# design.net
KiCad netlist of a schematic drawn in Altium Designer
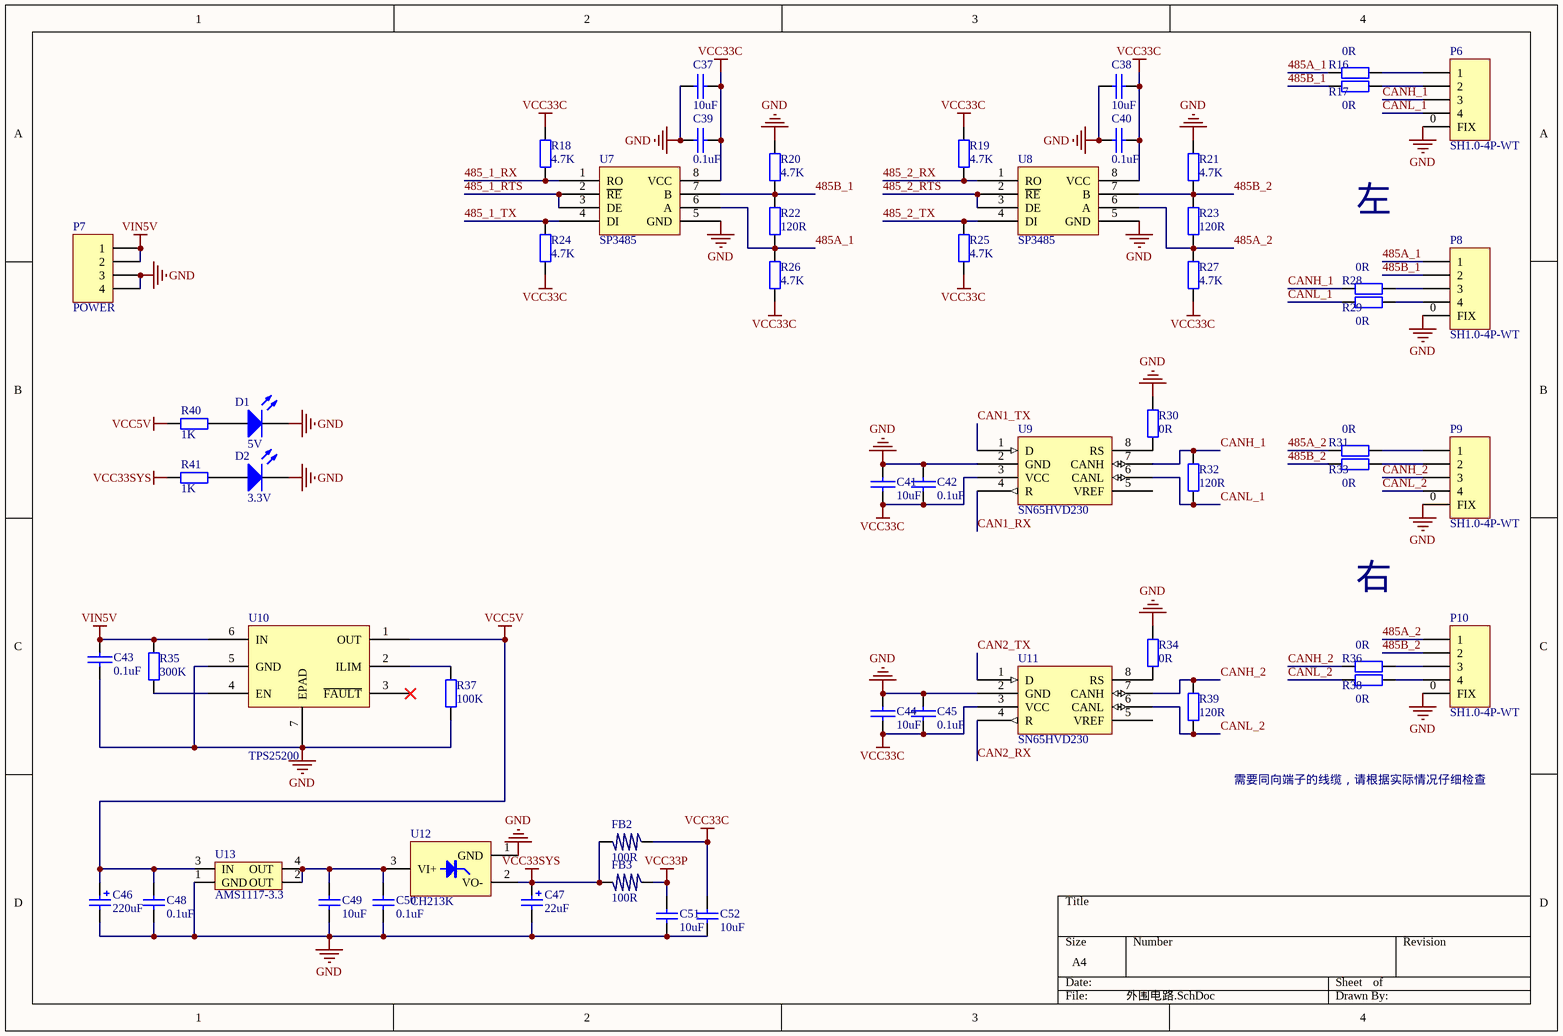
[diagram p0: 外围电路.SchDoc]

(export (version "E")
  (design (tool "Eeschema 10.0.6"))
  (components
    (comp (ref "C37")
      (value "10uF")
      (footprint "C0805_M")
      (description "Capacitor")
      (libsource (lib "*") (part "CAP"))
    )
    (comp (ref "C38")
      (value "10uF")
      (footprint "C0805_M")
      (description "Capacitor")
      (libsource (lib "*") (part "CAP"))
    )
    (comp (ref "C39")
      (value "0.1uF")
      (footprint "C0805_M")
      (description "Capacitor")
      (libsource (lib "*") (part "CAP"))
    )
    (comp (ref "C40")
      (value "0.1uF")
      (footprint "C0805_M")
      (description "Capacitor")
      (libsource (lib "*") (part "CAP"))
    )
    (comp (ref "C41")
      (value "10uF")
      (footprint "C0805_M")
      (description "Capacitor")
      (libsource (lib "*") (part "CAP"))
    )
    (comp (ref "C42")
      (value "0.1uF")
      (footprint "C0805_M")
      (description "Capacitor")
      (libsource (lib "*") (part "CAP"))
    )
    (comp (ref "C43")
      (value "0.1uF")
      (footprint "C0805_M")
      (description "Capacitor")
      (libsource (lib "*") (part "CAP"))
    )
    (comp (ref "C44")
      (value "10uF")
      (footprint "C0805_M")
      (description "Capacitor")
      (libsource (lib "*") (part "CAP"))
    )
    (comp (ref "C45")
      (value "0.1uF")
      (footprint "C0805_M")
      (description "Capacitor")
      (libsource (lib "*") (part "CAP"))
    )
    (comp (ref "C46")
      (value "220uF")
      (footprint "CS 6*6 - R")
      (description "Polarized Capacitor (Axial)")
      (fields (field (name "PUBLISHER") "Altium Limited"))
      (libsource (lib "Miscellaneous Devices") (part "Cap Pol2"))
    )
    (comp (ref "C47")
      (value "22uF")
      (footprint "CS 6*6 - R")
      (description "Polarized Capacitor (Axial)")
      (fields (field (name "PUBLISHER") "Altium Limited"))
      (libsource (lib "Miscellaneous Devices") (part "Cap Pol2"))
    )
    (comp (ref "C48")
      (value "0.1uF")
      (footprint "C0805_M")
      (description "Capacitor")
      (fields (field (name "PUBLISHER") "Altium Limited"))
      (libsource (lib "Miscellaneous Devices") (part "Cap"))
    )
    (comp (ref "C49")
      (value "10uF")
      (footprint "C0805_M")
      (description "Capacitor")
      (fields (field (name "PUBLISHER") "Altium Limited"))
      (libsource (lib "Miscellaneous Devices") (part "Cap"))
    )
    (comp (ref "C50")
      (value "0.1uF")
      (footprint "C0805_M")
      (description "Capacitor")
      (fields (field (name "PUBLISHER") "Altium Limited"))
      (libsource (lib "Miscellaneous Devices") (part "Cap"))
    )
    (comp (ref "C51")
      (value "10uF")
      (footprint "C0805_M")
      (description "Capacitor")
      (fields (field (name "PUBLISHER") "Altium Limited"))
      (libsource (lib "Miscellaneous Devices") (part "Cap"))
    )
    (comp (ref "C52")
      (value "10uF")
      (footprint "C0805_M")
      (description "Capacitor")
      (fields (field (name "PUBLISHER") "Altium Limited"))
      (libsource (lib "Miscellaneous Devices") (part "Cap"))
    )
    (comp (ref "D1")
      (value "5V")
      (footprint "LED0805_G")
      (description "Typical RED GaAs LED")
      (fields (field (name "PUBLISHER") "Altium Limited"))
      (libsource (lib "Miscellaneous Devices") (part "LED1"))
    )
    (comp (ref "D2")
      (value "3.3V")
      (footprint "LED0805_G")
      (description "Typical RED GaAs LED")
      (fields (field (name "PUBLISHER") "Altium Limited"))
      (libsource (lib "Miscellaneous Devices") (part "LED1"))
    )
    (comp (ref "FB2") (value "100R") (footprint "R0805_M") (libsource (lib "EXPLORER") (part "L")))
    (comp (ref "FB3") (value "100R") (footprint "R0805_M") (libsource (lib "EXPLORER") (part "L")))
    (comp (ref "P6")
      (value "SH1.0-4P-WT")
      (footprint "SH1.0-LT-4P")
      (description "Header, 5-Pin")
      (fields (field (name "PUBLISHER") "Altium Limited"))
      (libsource (lib "Miscellaneous Connectors") (part "Header 5"))
    )
    (comp (ref "P7")
      (value "POWER")
      (footprint "XH2.54-LI-4P")
      (description "Header, 4-Pin")
      (fields (field (name "PUBLISHER") "Altium Limited"))
      (libsource (lib "Miscellaneous Connectors") (part "Header 4"))
    )
    (comp (ref "P8")
      (value "SH1.0-4P-WT")
      (footprint "SH1.0-LT-4P")
      (description "Header, 5-Pin")
      (fields (field (name "PUBLISHER") "Altium Limited"))
      (libsource (lib "Miscellaneous Connectors") (part "Header 5"))
    )
    (comp (ref "P9")
      (value "SH1.0-4P-WT")
      (footprint "SH1.0-LT-4P")
      (description "Header, 5-Pin")
      (fields (field (name "PUBLISHER") "Altium Limited"))
      (libsource (lib "Miscellaneous Connectors") (part "Header 5"))
    )
    (comp (ref "P10")
      (value "SH1.0-4P-WT")
      (footprint "SH1.0-LT-4P")
      (description "Header, 5-Pin")
      (fields (field (name "PUBLISHER") "Altium Limited"))
      (libsource (lib "Miscellaneous Connectors") (part "Header 5"))
    )
    (comp (ref "R16")
      (value "0R")
      (footprint "R0805_M")
      (description "Resistor")
      (fields (field (name "PUBLISHER") "Altium Limited"))
      (libsource (lib "") (part "Res2_1"))
    )
    (comp (ref "R17")
      (value "0R")
      (footprint "R0805_M")
      (description "Resistor")
      (fields (field (name "PUBLISHER") "Altium Limited"))
      (libsource (lib "") (part "Res2_1"))
    )
    (comp (ref "R18")
      (value "4.7K")
      (footprint "R0805_M")
      (description "Resistor")
      (fields (field (name "PUBLISHER") "Altium Limited"))
      (libsource (lib "Miscellaneous Devices") (part "Res2"))
    )
    (comp (ref "R19")
      (value "4.7K")
      (footprint "R0805_M")
      (description "Resistor")
      (fields (field (name "PUBLISHER") "Altium Limited"))
      (libsource (lib "Miscellaneous Devices") (part "Res2"))
    )
    (comp (ref "R20")
      (value "4.7K")
      (footprint "R0805_M")
      (description "Resistor")
      (fields (field (name "PUBLISHER") "Altium Limited"))
      (libsource (lib "Miscellaneous Devices") (part "Res2"))
    )
    (comp (ref "R21")
      (value "4.7K")
      (footprint "R0805_M")
      (description "Resistor")
      (fields (field (name "PUBLISHER") "Altium Limited"))
      (libsource (lib "Miscellaneous Devices") (part "Res2"))
    )
    (comp (ref "R22")
      (value "120R")
      (footprint "R0805_M")
      (description "Resistor")
      (fields (field (name "PUBLISHER") "Altium Limited"))
      (libsource (lib "Miscellaneous Devices") (part "Res2"))
    )
    (comp (ref "R23")
      (value "120R")
      (footprint "R0805_M")
      (description "Resistor")
      (fields (field (name "PUBLISHER") "Altium Limited"))
      (libsource (lib "Miscellaneous Devices") (part "Res2"))
    )
    (comp (ref "R24")
      (value "4.7K")
      (footprint "R0805_M")
      (description "Resistor")
      (fields (field (name "PUBLISHER") "Altium Limited"))
      (libsource (lib "Miscellaneous Devices") (part "Res2"))
    )
    (comp (ref "R25")
      (value "4.7K")
      (footprint "R0805_M")
      (description "Resistor")
      (fields (field (name "PUBLISHER") "Altium Limited"))
      (libsource (lib "Miscellaneous Devices") (part "Res2"))
    )
    (comp (ref "R26")
      (value "4.7K")
      (footprint "R0805_M")
      (description "Resistor")
      (fields (field (name "PUBLISHER") "Altium Limited"))
      (libsource (lib "Miscellaneous Devices") (part "Res2"))
    )
    (comp (ref "R27")
      (value "4.7K")
      (footprint "R0805_M")
      (description "Resistor")
      (fields (field (name "PUBLISHER") "Altium Limited"))
      (libsource (lib "Miscellaneous Devices") (part "Res2"))
    )
    (comp (ref "R28")
      (value "0R")
      (footprint "R0805_M")
      (description "Resistor")
      (fields (field (name "PUBLISHER") "Altium Limited"))
      (libsource (lib "") (part "Res2_1"))
    )
    (comp (ref "R29")
      (value "0R")
      (footprint "R0805_M")
      (description "Resistor")
      (fields (field (name "PUBLISHER") "Altium Limited"))
      (libsource (lib "") (part "Res2_1"))
    )
    (comp (ref "R30")
      (value "0R")
      (footprint "R0805_M")
      (description "Resistor")
      (fields (field (name "PUBLISHER") "Altium Limited"))
      (libsource (lib "Miscellaneous Devices") (part "Res2"))
    )
    (comp (ref "R31")
      (value "0R")
      (footprint "R0805_M")
      (description "Resistor")
      (fields (field (name "PUBLISHER") "Altium Limited"))
      (libsource (lib "") (part "Res2_1"))
    )
    (comp (ref "R32")
      (value "120R")
      (footprint "R0805_M")
      (description "Resistor")
      (fields (field (name "PUBLISHER") "Altium Limited"))
      (libsource (lib "Miscellaneous Devices") (part "Res2"))
    )
    (comp (ref "R33")
      (value "0R")
      (footprint "R0805_M")
      (description "Resistor")
      (fields (field (name "PUBLISHER") "Altium Limited"))
      (libsource (lib "") (part "Res2_1"))
    )
    (comp (ref "R34")
      (value "0R")
      (footprint "R0805_M")
      (description "Resistor")
      (fields (field (name "PUBLISHER") "Altium Limited"))
      (libsource (lib "Miscellaneous Devices") (part "Res2"))
    )
    (comp (ref "R35")
      (value "300K")
      (footprint "R0805_M")
      (description "Resistor")
      (fields (field (name "PUBLISHER") "Altium Limited"))
      (libsource (lib "Miscellaneous Devices") (part "Res2"))
    )
    (comp (ref "R36")
      (value "0R")
      (footprint "R0805_M")
      (description "Resistor")
      (fields (field (name "PUBLISHER") "Altium Limited"))
      (libsource (lib "") (part "Res2_1"))
    )
    (comp (ref "R37")
      (value "100K")
      (footprint "R0805_M")
      (description "Resistor")
      (fields (field (name "PUBLISHER") "Altium Limited"))
      (libsource (lib "Miscellaneous Devices") (part "Res2"))
    )
    (comp (ref "R38")
      (value "0R")
      (footprint "R0805_M")
      (description "Resistor")
      (fields (field (name "PUBLISHER") "Altium Limited"))
      (libsource (lib "") (part "Res2_1"))
    )
    (comp (ref "R39")
      (value "120R")
      (footprint "R0805_M")
      (description "Resistor")
      (fields (field (name "PUBLISHER") "Altium Limited"))
      (libsource (lib "Miscellaneous Devices") (part "Res2"))
    )
    (comp (ref "R40")
      (value "1K")
      (footprint "R0805_M")
      (description "Resistor")
      (fields (field (name "PUBLISHER") "Altium Limited"))
      (libsource (lib "") (part "Res2_1"))
    )
    (comp (ref "R41")
      (value "1K")
      (footprint "R0805_M")
      (description "Resistor")
      (fields (field (name "PUBLISHER") "Altium Limited"))
      (libsource (lib "") (part "Res2_1"))
    )
    (comp (ref "U7") (value "SP3485") (footprint "SOIC-8") (libsource (lib "XL6005") (part "SP3485")))
    (comp (ref "U8") (value "SP3485") (footprint "SOIC-8") (libsource (lib "XL6005") (part "SP3485")))
    (comp (ref "U9")
      (value "SN65HVD230")
      (footprint "SOIC-8")
      (libsource (lib "XL6005") (part "SN65HVD230/1"))
    )
    (comp (ref "U10")
      (value "TPS25200")
      (footprint "WSON-6")
      (libsource (lib "7688A原理图封装") (part "TPS25200"))
    )
    (comp (ref "U11")
      (value "SN65HVD230")
      (footprint "SOIC-8")
      (libsource (lib "XL6005") (part "SN65HVD230/1"))
    )
    (comp (ref "U12")
      (value "CH213K")
      (footprint "SOT-23-3")
      (description "Ideal Diode 5V*1A")
      (libsource (lib "CHXXX") (part "CH213K"))
    )
    (comp (ref "U13")
      (value "AMS1117-3.3")
      (footprint "2.02-SOT封装:SOT223_M")
      (libsource (lib "Explorer STM32F407封装库") (part "AMS1117"))
    )
  )
  (nets
    (net (code "1") (name "/485A_1") (class "Default")
      (node (ref "P8") (pin "1") (pinfunction "1_1") (pintype "passive"))
      (node (ref "R16") (pin "2") (pinfunction "2_2") (pintype "passive"))
      (node (ref "R22") (pin "1") (pinfunction "1_1") (pintype "passive"))
      (node (ref "R26") (pin "2") (pinfunction "2_2") (pintype "passive"))
      (node (ref "U7") (pin "6") (pinfunction "A_6") (pintype "passive"))
    )
    (net (code "2") (name "/485A_2") (class "Default")
      (node (ref "P10") (pin "1") (pinfunction "1_1") (pintype "passive"))
      (node (ref "R23") (pin "1") (pinfunction "1_1") (pintype "passive"))
      (node (ref "R27") (pin "2") (pinfunction "2_2") (pintype "passive"))
      (node (ref "R31") (pin "2") (pinfunction "2_2") (pintype "passive"))
      (node (ref "U8") (pin "6") (pinfunction "A_6") (pintype "passive"))
    )
    (net (code "3") (name "/485B_1") (class "Default")
      (node (ref "P8") (pin "2") (pinfunction "2_2") (pintype "passive"))
      (node (ref "R17") (pin "2") (pinfunction "2_2") (pintype "passive"))
      (node (ref "R20") (pin "1") (pinfunction "1_1") (pintype "passive"))
      (node (ref "R22") (pin "2") (pinfunction "2_2") (pintype "passive"))
      (node (ref "U7") (pin "7") (pinfunction "B_7") (pintype "passive"))
    )
    (net (code "4") (name "/485B_2") (class "Default")
      (node (ref "P10") (pin "2") (pinfunction "2_2") (pintype "passive"))
      (node (ref "R21") (pin "1") (pinfunction "1_1") (pintype "passive"))
      (node (ref "R23") (pin "2") (pinfunction "2_2") (pintype "passive"))
      (node (ref "R33") (pin "2") (pinfunction "2_2") (pintype "passive"))
      (node (ref "U8") (pin "7") (pinfunction "B_7") (pintype "passive"))
    )
    (net (code "5") (name "/485_1_RTS") (class "Default")
      (node (ref "U7") (pin "2") (pinfunction "~{RE}_2") (pintype "passive"))
      (node (ref "U7") (pin "3") (pinfunction "DE_3") (pintype "passive"))
    )
    (net (code "6") (name "/485_1_RX") (class "Default")
      (node (ref "R18") (pin "1") (pinfunction "1_1") (pintype "passive"))
      (node (ref "U7") (pin "1") (pinfunction "RO_1") (pintype "passive"))
    )
    (net (code "7") (name "/485_1_TX") (class "Default")
      (node (ref "R24") (pin "2") (pinfunction "2_2") (pintype "passive"))
      (node (ref "U7") (pin "4") (pinfunction "DI_4") (pintype "passive"))
    )
    (net (code "8") (name "/485_2_RTS") (class "Default")
      (node (ref "U8") (pin "2") (pinfunction "~{RE}_2") (pintype "passive"))
      (node (ref "U8") (pin "3") (pinfunction "DE_3") (pintype "passive"))
    )
    (net (code "9") (name "/485_2_RX") (class "Default")
      (node (ref "R19") (pin "1") (pinfunction "1_1") (pintype "passive"))
      (node (ref "U8") (pin "1") (pinfunction "RO_1") (pintype "passive"))
    )
    (net (code "10") (name "/485_2_TX") (class "Default")
      (node (ref "R25") (pin "2") (pinfunction "2_2") (pintype "passive"))
      (node (ref "U8") (pin "4") (pinfunction "DI_4") (pintype "passive"))
    )
    (net (code "11") (name "/CAN1_RX") (class "Default")
      (node (ref "U9") (pin "4") (pinfunction "R_4") (pintype "output"))
    )
    (net (code "12") (name "/CAN1_TX") (class "Default")
      (node (ref "U9") (pin "1") (pinfunction "D_1") (pintype "input"))
    )
    (net (code "13") (name "/CAN2_RX") (class "Default")
      (node (ref "U11") (pin "4") (pinfunction "R_4") (pintype "output"))
    )
    (net (code "14") (name "/CAN2_TX") (class "Default")
      (node (ref "U11") (pin "1") (pinfunction "D_1") (pintype "input"))
    )
    (net (code "15") (name "/CANH_1") (class "Default")
      (node (ref "P6") (pin "3") (pinfunction "3_3") (pintype "passive"))
      (node (ref "R28") (pin "2") (pinfunction "2_2") (pintype "passive"))
      (node (ref "R32") (pin "2") (pinfunction "2_2") (pintype "passive"))
      (node (ref "U9") (pin "7") (pinfunction "CANH_7") (pintype "bidirectional"))
    )
    (net (code "16") (name "/CANH_2") (class "Default")
      (node (ref "P9") (pin "3") (pinfunction "3_3") (pintype "passive"))
      (node (ref "R36") (pin "2") (pinfunction "2_2") (pintype "passive"))
      (node (ref "R39") (pin "2") (pinfunction "2_2") (pintype "passive"))
      (node (ref "U11") (pin "7") (pinfunction "CANH_7") (pintype "bidirectional"))
    )
    (net (code "17") (name "/CANL_1") (class "Default")
      (node (ref "P6") (pin "4") (pinfunction "4_4") (pintype "passive"))
      (node (ref "R29") (pin "2") (pinfunction "2_2") (pintype "passive"))
      (node (ref "R32") (pin "1") (pinfunction "1_1") (pintype "passive"))
      (node (ref "U9") (pin "6") (pinfunction "CANL_6") (pintype "bidirectional"))
    )
    (net (code "18") (name "/CANL_2") (class "Default")
      (node (ref "P9") (pin "4") (pinfunction "4_4") (pintype "passive"))
      (node (ref "R38") (pin "2") (pinfunction "2_2") (pintype "passive"))
      (node (ref "R39") (pin "1") (pinfunction "1_1") (pintype "passive"))
      (node (ref "U11") (pin "6") (pinfunction "CANL_6") (pintype "bidirectional"))
    )
    (net (code "19") (name "GND") (class "Default")
      (node (ref "C37") (pin "1") (pinfunction "1_1") (pintype "passive"))
      (node (ref "C38") (pin "1") (pinfunction "1_1") (pintype "passive"))
      (node (ref "C39") (pin "1") (pinfunction "1_1") (pintype "passive"))
      (node (ref "C40") (pin "1") (pinfunction "1_1") (pintype "passive"))
      (node (ref "C41") (pin "2") (pinfunction "2_2") (pintype "passive"))
      (node (ref "C42") (pin "2") (pinfunction "2_2") (pintype "passive"))
      (node (ref "C43") (pin "2") (pinfunction "2_2") (pintype "passive"))
      (node (ref "C44") (pin "2") (pinfunction "2_2") (pintype "passive"))
      (node (ref "C45") (pin "2") (pinfunction "2_2") (pintype "passive"))
      (node (ref "C46") (pin "2") (pinfunction "2_2") (pintype "passive"))
      (node (ref "C47") (pin "2") (pinfunction "2_2") (pintype "passive"))
      (node (ref "C48") (pin "1") (pinfunction "1_1") (pintype "passive"))
      (node (ref "C49") (pin "1") (pinfunction "1_1") (pintype "passive"))
      (node (ref "C50") (pin "1") (pinfunction "1_1") (pintype "passive"))
      (node (ref "C51") (pin "1") (pinfunction "1_1") (pintype "passive"))
      (node (ref "C52") (pin "1") (pinfunction "1_1") (pintype "passive"))
      (node (ref "D1") (pin "2") (pinfunction "K_2") (pintype "passive"))
      (node (ref "D2") (pin "2") (pinfunction "K_2") (pintype "passive"))
      (node (ref "P10") (pin "0") (pinfunction "FIX_0") (pintype "passive"))
      (node (ref "P6") (pin "0") (pinfunction "FIX_0") (pintype "passive"))
      (node (ref "P7") (pin "3") (pinfunction "3_3") (pintype "passive"))
      (node (ref "P7") (pin "4") (pinfunction "4_4") (pintype "passive"))
      (node (ref "P8") (pin "0") (pinfunction "FIX_0") (pintype "passive"))
      (node (ref "P9") (pin "0") (pinfunction "FIX_0") (pintype "passive"))
      (node (ref "R20") (pin "2") (pinfunction "2_2") (pintype "passive"))
      (node (ref "R21") (pin "2") (pinfunction "2_2") (pintype "passive"))
      (node (ref "R30") (pin "2") (pinfunction "2_2") (pintype "passive"))
      (node (ref "R34") (pin "2") (pinfunction "2_2") (pintype "passive"))
      (node (ref "R37") (pin "1") (pinfunction "1_1") (pintype "passive"))
      (node (ref "U10") (pin "5") (pinfunction "GND_5") (pintype "passive"))
      (node (ref "U10") (pin "7") (pinfunction "EPAD_7") (pintype "passive"))
      (node (ref "U11") (pin "2") (pinfunction "GND_2") (pintype "passive"))
      (node (ref "U12") (pin "1") (pinfunction "GND_1") (pintype "power_in"))
      (node (ref "U13") (pin "1") (pinfunction "GND_1") (pintype "passive"))
      (node (ref "U7") (pin "5") (pinfunction "GND_5") (pintype "passive"))
      (node (ref "U8") (pin "5") (pinfunction "GND_5") (pintype "passive"))
      (node (ref "U9") (pin "2") (pinfunction "GND_2") (pintype "passive"))
    )
    (net (code "20") (name "Net-(D1-A)") (class "Default")
      (node (ref "D1") (pin "1") (pinfunction "A_1") (pintype "passive"))
      (node (ref "R40") (pin "1") (pinfunction "1_1") (pintype "passive"))
    )
    (net (code "21") (name "Net-(D2-A)") (class "Default")
      (node (ref "D2") (pin "1") (pinfunction "A_1") (pintype "passive"))
      (node (ref "R41") (pin "1") (pinfunction "1_1") (pintype "passive"))
    )
    (net (code "22") (name "Net-(P6-Pad1)") (class "Default")
      (node (ref "P6") (pin "1") (pinfunction "1_1") (pintype "passive"))
      (node (ref "R16") (pin "1") (pinfunction "1_1") (pintype "passive"))
    )
    (net (code "23") (name "Net-(P6-Pad2)") (class "Default")
      (node (ref "P6") (pin "2") (pinfunction "2_2") (pintype "passive"))
      (node (ref "R17") (pin "1") (pinfunction "1_1") (pintype "passive"))
    )
    (net (code "24") (name "Net-(P8-Pad3)") (class "Default")
      (node (ref "P8") (pin "3") (pinfunction "3_3") (pintype "passive"))
      (node (ref "R28") (pin "1") (pinfunction "1_1") (pintype "passive"))
    )
    (net (code "25") (name "Net-(P8-Pad4)") (class "Default")
      (node (ref "P8") (pin "4") (pinfunction "4_4") (pintype "passive"))
      (node (ref "R29") (pin "1") (pinfunction "1_1") (pintype "passive"))
    )
    (net (code "26") (name "Net-(P9-Pad1)") (class "Default")
      (node (ref "P9") (pin "1") (pinfunction "1_1") (pintype "passive"))
      (node (ref "R31") (pin "1") (pinfunction "1_1") (pintype "passive"))
    )
    (net (code "27") (name "Net-(P9-Pad2)") (class "Default")
      (node (ref "P9") (pin "2") (pinfunction "2_2") (pintype "passive"))
      (node (ref "R33") (pin "1") (pinfunction "1_1") (pintype "passive"))
    )
    (net (code "28") (name "Net-(P10-Pad3)") (class "Default")
      (node (ref "P10") (pin "3") (pinfunction "3_3") (pintype "passive"))
      (node (ref "R36") (pin "1") (pinfunction "1_1") (pintype "passive"))
    )
    (net (code "29") (name "Net-(P10-Pad4)") (class "Default")
      (node (ref "P10") (pin "4") (pinfunction "4_4") (pintype "passive"))
      (node (ref "R38") (pin "1") (pinfunction "1_1") (pintype "passive"))
    )
    (net (code "30") (name "Net-(U9-RS)") (class "Default")
      (node (ref "R30") (pin "1") (pinfunction "1_1") (pintype "passive"))
      (node (ref "U9") (pin "8") (pinfunction "RS_8") (pintype "passive"))
    )
    (net (code "31") (name "Net-(U10-EN)") (class "Default")
      (node (ref "R35") (pin "1") (pinfunction "1_1") (pintype "passive"))
      (node (ref "U10") (pin "4") (pinfunction "EN_4") (pintype "passive"))
    )
    (net (code "32") (name "Net-(U10-ILIM)") (class "Default")
      (node (ref "R37") (pin "2") (pinfunction "2_2") (pintype "passive"))
      (node (ref "U10") (pin "2") (pinfunction "ILIM_2") (pintype "passive"))
    )
    (net (code "33") (name "Net-(U11-RS)") (class "Default")
      (node (ref "R34") (pin "1") (pinfunction "1_1") (pintype "passive"))
      (node (ref "U11") (pin "8") (pinfunction "RS_8") (pintype "passive"))
    )
    (net (code "34") (name "Net-(U12-VI+)") (class "Default")
      (node (ref "C49") (pin "2") (pinfunction "2_2") (pintype "passive"))
      (node (ref "C50") (pin "2") (pinfunction "2_2") (pintype "passive"))
      (node (ref "U12") (pin "3") (pinfunction "VI+_3") (pintype "power_in"))
      (node (ref "U13") (pin "2") (pinfunction "OUT_2") (pintype "passive"))
      (node (ref "U13") (pin "4") (pinfunction "OUT_4") (pintype "passive"))
    )
    (net (code "35") (name "VCC5V") (class "Default")
      (node (ref "C46") (pin "1") (pinfunction "1_1") (pintype "passive"))
      (node (ref "C48") (pin "2") (pinfunction "2_2") (pintype "passive"))
      (node (ref "R40") (pin "2") (pinfunction "2_2") (pintype "passive"))
      (node (ref "U10") (pin "1") (pinfunction "OUT_1") (pintype "passive"))
      (node (ref "U13") (pin "3") (pinfunction "IN_3") (pintype "passive"))
    )
    (net (code "36") (name "VCC33C") (class "Default")
      (node (ref "C37") (pin "2") (pinfunction "2_2") (pintype "passive"))
      (node (ref "C38") (pin "2") (pinfunction "2_2") (pintype "passive"))
      (node (ref "C39") (pin "2") (pinfunction "2_2") (pintype "passive"))
      (node (ref "C40") (pin "2") (pinfunction "2_2") (pintype "passive"))
      (node (ref "C41") (pin "1") (pinfunction "1_1") (pintype "passive"))
      (node (ref "C42") (pin "1") (pinfunction "1_1") (pintype "passive"))
      (node (ref "C44") (pin "1") (pinfunction "1_1") (pintype "passive"))
      (node (ref "C45") (pin "1") (pinfunction "1_1") (pintype "passive"))
      (node (ref "C52") (pin "2") (pinfunction "2_2") (pintype "passive"))
      (node (ref "FB2") (pin "1") (pintype "passive"))
      (node (ref "R18") (pin "2") (pinfunction "2_2") (pintype "passive"))
      (node (ref "R19") (pin "2") (pinfunction "2_2") (pintype "passive"))
      (node (ref "R24") (pin "1") (pinfunction "1_1") (pintype "passive"))
      (node (ref "R25") (pin "1") (pinfunction "1_1") (pintype "passive"))
      (node (ref "R26") (pin "1") (pinfunction "1_1") (pintype "passive"))
      (node (ref "R27") (pin "1") (pinfunction "1_1") (pintype "passive"))
      (node (ref "U11") (pin "3") (pinfunction "VCC_3") (pintype "passive"))
      (node (ref "U7") (pin "8") (pinfunction "VCC_8") (pintype "passive"))
      (node (ref "U8") (pin "8") (pinfunction "VCC_8") (pintype "passive"))
      (node (ref "U9") (pin "3") (pinfunction "VCC_3") (pintype "passive"))
    )
    (net (code "37") (name "VCC33P") (class "Default")
      (node (ref "C51") (pin "2") (pinfunction "2_2") (pintype "passive"))
      (node (ref "FB3") (pin "1") (pintype "passive"))
    )
    (net (code "38") (name "VCC33SYS") (class "Default")
      (node (ref "C47") (pin "1") (pinfunction "1_1") (pintype "passive"))
      (node (ref "FB2") (pin "2") (pintype "passive"))
      (node (ref "FB3") (pin "2") (pintype "passive"))
      (node (ref "R41") (pin "2") (pinfunction "2_2") (pintype "passive"))
      (node (ref "U12") (pin "2") (pinfunction "VO-_2") (pintype "power_in"))
    )
    (net (code "39") (name "VIN5V") (class "Default")
      (node (ref "C43") (pin "1") (pinfunction "1_1") (pintype "passive"))
      (node (ref "P7") (pin "1") (pinfunction "1_1") (pintype "passive"))
      (node (ref "P7") (pin "2") (pinfunction "2_2") (pintype "passive"))
      (node (ref "R35") (pin "2") (pinfunction "2_2") (pintype "passive"))
      (node (ref "U10") (pin "6") (pinfunction "IN_6") (pintype "passive"))
    )
    (net (code "40") (name "unconnected-(U9-VREF-Pad5)") (class "Default")
      (node (ref "U9") (pin "5") (pinfunction "VREF_5") (pintype "passive"))
    )
    (net (code "41") (name "unconnected-(U10-~{FAULT}-Pad3)") (class "Default")
      (node (ref "U10") (pin "3") (pinfunction "~{FAULT}_3") (pintype "passive+no_connect"))
    )
    (net (code "42") (name "unconnected-(U11-VREF-Pad5)") (class "Default")
      (node (ref "U11") (pin "5") (pinfunction "VREF_5") (pintype "passive"))
    )
  )
)
